# led-segment-display.net
KiCad netlist of a schematic drawn in EAGLE
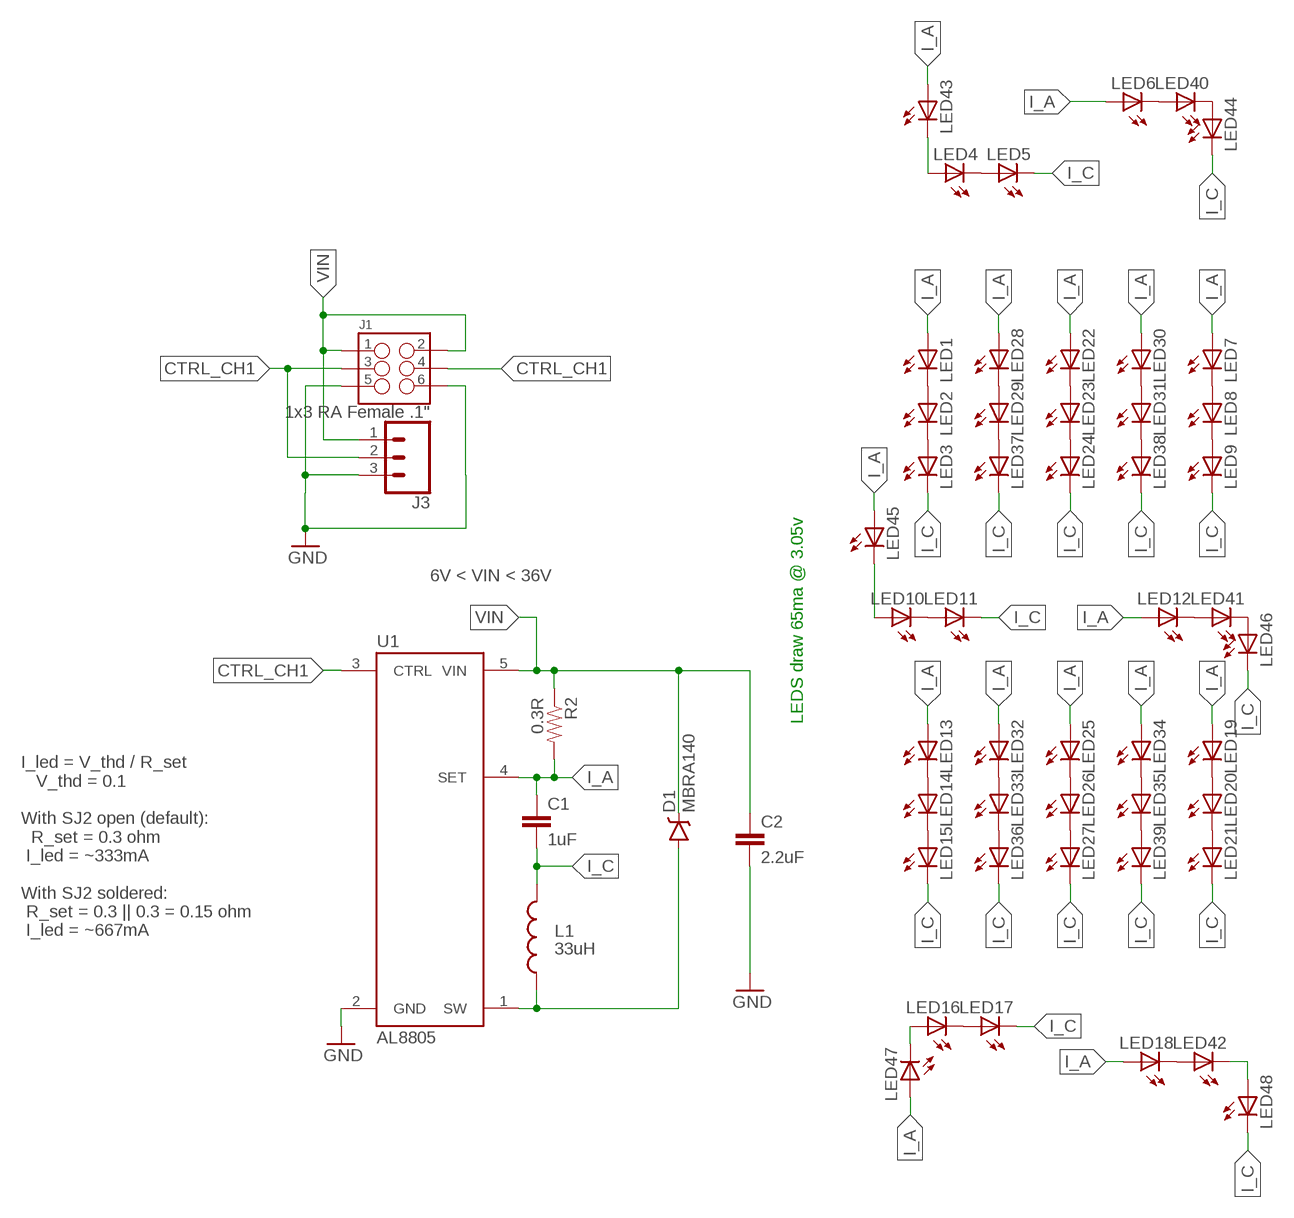
[diagram p0: schematic, sheet 1]

(export (version "E")
  (design (tool "Eeschema 10.0.6"))
  (components
    (comp (ref "C1")
      (value "1uF")
      (footprint "eagle-import:1206-CAP")
      (libsource (lib "eagle-import") (part "1.0UF50V10%(1206)"))
    )
    (comp (ref "C2")
      (value "2.2uF")
      (footprint "eagle-import:1206-CAP")
      (libsource (lib "eagle-import") (part "2.2UF50V10%(1206)"))
    )
    (comp (ref "D1")
      (value "MBRA140")
      (footprint "eagle-import:SMA-DIODE")
      (libsource (lib "eagle-import") (part "DIODE-SCHOTTKY-MBRA140"))
    )
    (comp (ref "J1")
      (value "M03X2SMD")
      (footprint "eagle-import:2X3_SMD_2.54MM")
      (libsource (lib "eagle-import") (part "M03X2SMD"))
    )
    (comp (ref "J3")
      (value "1x3 RA Female .1\"")
      (footprint "eagle-import:1X3_SMD_2.54MM")
      (libsource (lib "eagle-import") (part "CONN_03SMD_RA_2.54MM"))
    )
    (comp (ref "L1")
      (value "33uH")
      (footprint "eagle-import:SRN6045")
      (libsource (lib "eagle-import") (part "INDUCTORBOURNS_SRN6045"))
    )
    (comp (ref "LED1")
      (value "LED3014")
      (footprint "eagle-import:LED-3014")
      (libsource (lib "eagle-import") (part "LED3014"))
    )
    (comp (ref "LED2")
      (value "LED3014")
      (footprint "eagle-import:LED-3014")
      (libsource (lib "eagle-import") (part "LED3014"))
    )
    (comp (ref "LED3")
      (value "LED3014")
      (footprint "eagle-import:LED-3014")
      (libsource (lib "eagle-import") (part "LED3014"))
    )
    (comp (ref "LED4")
      (value "LED3014")
      (footprint "eagle-import:LED-3014")
      (libsource (lib "eagle-import") (part "LED3014"))
    )
    (comp (ref "LED5")
      (value "LED3014")
      (footprint "eagle-import:LED-3014")
      (libsource (lib "eagle-import") (part "LED3014"))
    )
    (comp (ref "LED6")
      (value "LED3014")
      (footprint "eagle-import:LED-3014")
      (libsource (lib "eagle-import") (part "LED3014"))
    )
    (comp (ref "LED7")
      (value "LED3014")
      (footprint "eagle-import:LED-3014")
      (libsource (lib "eagle-import") (part "LED3014"))
    )
    (comp (ref "LED8")
      (value "LED3014")
      (footprint "eagle-import:LED-3014")
      (libsource (lib "eagle-import") (part "LED3014"))
    )
    (comp (ref "LED9")
      (value "LED3014")
      (footprint "eagle-import:LED-3014")
      (libsource (lib "eagle-import") (part "LED3014"))
    )
    (comp (ref "LED10")
      (value "LED3014")
      (footprint "eagle-import:LED-3014")
      (libsource (lib "eagle-import") (part "LED3014"))
    )
    (comp (ref "LED11")
      (value "LED3014")
      (footprint "eagle-import:LED-3014")
      (libsource (lib "eagle-import") (part "LED3014"))
    )
    (comp (ref "LED12")
      (value "LED3014")
      (footprint "eagle-import:LED-3014")
      (libsource (lib "eagle-import") (part "LED3014"))
    )
    (comp (ref "LED13")
      (value "LED3014")
      (footprint "eagle-import:LED-3014")
      (libsource (lib "eagle-import") (part "LED3014"))
    )
    (comp (ref "LED14")
      (value "LED3014")
      (footprint "eagle-import:LED-3014")
      (libsource (lib "eagle-import") (part "LED3014"))
    )
    (comp (ref "LED15")
      (value "LED3014")
      (footprint "eagle-import:LED-3014")
      (libsource (lib "eagle-import") (part "LED3014"))
    )
    (comp (ref "LED16")
      (value "LED3014")
      (footprint "eagle-import:LED-3014")
      (libsource (lib "eagle-import") (part "LED3014"))
    )
    (comp (ref "LED17")
      (value "LED3014")
      (footprint "eagle-import:LED-3014")
      (libsource (lib "eagle-import") (part "LED3014"))
    )
    (comp (ref "LED18")
      (value "LED3014")
      (footprint "eagle-import:LED-3014")
      (libsource (lib "eagle-import") (part "LED3014"))
    )
    (comp (ref "LED19")
      (value "LED3014")
      (footprint "eagle-import:LED-3014")
      (libsource (lib "eagle-import") (part "LED3014"))
    )
    (comp (ref "LED20")
      (value "LED3014")
      (footprint "eagle-import:LED-3014")
      (libsource (lib "eagle-import") (part "LED3014"))
    )
    (comp (ref "LED21")
      (value "LED3014")
      (footprint "eagle-import:LED-3014")
      (libsource (lib "eagle-import") (part "LED3014"))
    )
    (comp (ref "LED22")
      (value "LED3014")
      (footprint "eagle-import:LED-3014")
      (libsource (lib "eagle-import") (part "LED3014"))
    )
    (comp (ref "LED23")
      (value "LED3014")
      (footprint "eagle-import:LED-3014")
      (libsource (lib "eagle-import") (part "LED3014"))
    )
    (comp (ref "LED24")
      (value "LED3014")
      (footprint "eagle-import:LED-3014")
      (libsource (lib "eagle-import") (part "LED3014"))
    )
    (comp (ref "LED25")
      (value "LED3014")
      (footprint "eagle-import:LED-3014")
      (libsource (lib "eagle-import") (part "LED3014"))
    )
    (comp (ref "LED26")
      (value "LED3014")
      (footprint "eagle-import:LED-3014")
      (libsource (lib "eagle-import") (part "LED3014"))
    )
    (comp (ref "LED27")
      (value "LED3014")
      (footprint "eagle-import:LED-3014")
      (libsource (lib "eagle-import") (part "LED3014"))
    )
    (comp (ref "LED28")
      (value "LED3014")
      (footprint "eagle-import:LED-3014")
      (libsource (lib "eagle-import") (part "LED3014"))
    )
    (comp (ref "LED29")
      (value "LED3014")
      (footprint "eagle-import:LED-3014")
      (libsource (lib "eagle-import") (part "LED3014"))
    )
    (comp (ref "LED30")
      (value "LED3014")
      (footprint "eagle-import:LED-3014")
      (libsource (lib "eagle-import") (part "LED3014"))
    )
    (comp (ref "LED31")
      (value "LED3014")
      (footprint "eagle-import:LED-3014")
      (libsource (lib "eagle-import") (part "LED3014"))
    )
    (comp (ref "LED32")
      (value "LED3014")
      (footprint "eagle-import:LED-3014")
      (libsource (lib "eagle-import") (part "LED3014"))
    )
    (comp (ref "LED33")
      (value "LED3014")
      (footprint "eagle-import:LED-3014")
      (libsource (lib "eagle-import") (part "LED3014"))
    )
    (comp (ref "LED34")
      (value "LED3014")
      (footprint "eagle-import:LED-3014")
      (libsource (lib "eagle-import") (part "LED3014"))
    )
    (comp (ref "LED35")
      (value "LED3014")
      (footprint "eagle-import:LED-3014")
      (libsource (lib "eagle-import") (part "LED3014"))
    )
    (comp (ref "LED36")
      (value "LED3014")
      (footprint "eagle-import:LED-3014")
      (libsource (lib "eagle-import") (part "LED3014"))
    )
    (comp (ref "LED37")
      (value "LED3014")
      (footprint "eagle-import:LED-3014")
      (libsource (lib "eagle-import") (part "LED3014"))
    )
    (comp (ref "LED38")
      (value "LED3014")
      (footprint "eagle-import:LED-3014")
      (libsource (lib "eagle-import") (part "LED3014"))
    )
    (comp (ref "LED39")
      (value "LED3014")
      (footprint "eagle-import:LED-3014")
      (libsource (lib "eagle-import") (part "LED3014"))
    )
    (comp (ref "LED40")
      (value "LED3014")
      (footprint "eagle-import:LED-3014")
      (libsource (lib "eagle-import") (part "LED3014"))
    )
    (comp (ref "LED41")
      (value "LED3014")
      (footprint "eagle-import:LED-3014")
      (libsource (lib "eagle-import") (part "LED3014"))
    )
    (comp (ref "LED42")
      (value "LED3014")
      (footprint "eagle-import:LED-3014")
      (libsource (lib "eagle-import") (part "LED3014"))
    )
    (comp (ref "LED43")
      (value "LED3014")
      (footprint "eagle-import:LED-3014")
      (libsource (lib "eagle-import") (part "LED3014"))
    )
    (comp (ref "LED44")
      (value "LED3014")
      (footprint "eagle-import:LED-3014")
      (libsource (lib "eagle-import") (part "LED3014"))
    )
    (comp (ref "LED45")
      (value "LED3014")
      (footprint "eagle-import:LED-3014")
      (libsource (lib "eagle-import") (part "LED3014"))
    )
    (comp (ref "LED46")
      (value "LED3014")
      (footprint "eagle-import:LED-3014")
      (libsource (lib "eagle-import") (part "LED3014"))
    )
    (comp (ref "LED47")
      (value "LED3014")
      (footprint "eagle-import:LED-3014")
      (libsource (lib "eagle-import") (part "LED3014"))
    )
    (comp (ref "LED48")
      (value "LED3014")
      (footprint "eagle-import:LED-3014")
      (libsource (lib "eagle-import") (part "LED3014"))
    )
    (comp (ref "R2")
      (value "0.3R")
      (footprint "eagle-import:0805")
      (libsource (lib "eagle-import") (part "0.3OHM-1/8W-1%(0805)"))
    )
    (comp (ref "U1")
      (value "AL8805")
      (footprint "eagle-import:SOT23-5")
      (libsource (lib "eagle-import") (part "AL8805"))
    )
  )
  (nets
    (net (code "1") (name "CTRL_CH1") (class "Default")
      (node (ref "J1") (pin "3") (pinfunction "3_3") (pintype "bidirectional"))
      (node (ref "J1") (pin "4") (pinfunction "4_4") (pintype "bidirectional"))
      (node (ref "J3") (pin "2") (pinfunction "2_2") (pintype "passive"))
      (node (ref "U1") (pin "3") (pinfunction "CTRL_3") (pintype "bidirectional"))
    )
    (net (code "2") (name "GND") (class "Default")
      (node (ref "C2") (pin "2") (pinfunction "2_2") (pintype "passive"))
      (node (ref "J1") (pin "5") (pinfunction "5_5") (pintype "bidirectional"))
      (node (ref "J1") (pin "6") (pinfunction "6_6") (pintype "bidirectional"))
      (node (ref "J3") (pin "3") (pinfunction "3_3") (pintype "passive"))
      (node (ref "U1") (pin "2") (pinfunction "GND_2") (pintype "bidirectional"))
    )
    (net (code "3") (name "I_A") (class "Default")
      (node (ref "C1") (pin "1") (pinfunction "1_1") (pintype "passive"))
      (node (ref "LED1") (pin "A") (pinfunction "A_A") (pintype "passive"))
      (node (ref "LED12") (pin "A") (pinfunction "A_A") (pintype "passive"))
      (node (ref "LED13") (pin "A") (pinfunction "A_A") (pintype "passive"))
      (node (ref "LED18") (pin "A") (pinfunction "A_A") (pintype "passive"))
      (node (ref "LED19") (pin "A") (pinfunction "A_A") (pintype "passive"))
      (node (ref "LED22") (pin "A") (pinfunction "A_A") (pintype "passive"))
      (node (ref "LED25") (pin "A") (pinfunction "A_A") (pintype "passive"))
      (node (ref "LED28") (pin "A") (pinfunction "A_A") (pintype "passive"))
      (node (ref "LED30") (pin "A") (pinfunction "A_A") (pintype "passive"))
      (node (ref "LED32") (pin "A") (pinfunction "A_A") (pintype "passive"))
      (node (ref "LED34") (pin "A") (pinfunction "A_A") (pintype "passive"))
      (node (ref "LED43") (pin "A") (pinfunction "A_A") (pintype "passive"))
      (node (ref "LED45") (pin "A") (pinfunction "A_A") (pintype "passive"))
      (node (ref "LED47") (pin "A") (pinfunction "A_A") (pintype "passive"))
      (node (ref "LED6") (pin "A") (pinfunction "A_A") (pintype "passive"))
      (node (ref "LED7") (pin "A") (pinfunction "A_A") (pintype "passive"))
      (node (ref "R2") (pin "2") (pinfunction "2_2") (pintype "passive"))
      (node (ref "U1") (pin "4") (pinfunction "SET_4") (pintype "bidirectional"))
    )
    (net (code "4") (name "I_C") (class "Default")
      (node (ref "C1") (pin "2") (pinfunction "2_2") (pintype "passive"))
      (node (ref "L1") (pin "2") (pinfunction "2_2") (pintype "passive"))
      (node (ref "LED11") (pin "C") (pinfunction "C_C") (pintype "passive"))
      (node (ref "LED15") (pin "C") (pinfunction "C_C") (pintype "passive"))
      (node (ref "LED17") (pin "C") (pinfunction "C_C") (pintype "passive"))
      (node (ref "LED21") (pin "C") (pinfunction "C_C") (pintype "passive"))
      (node (ref "LED24") (pin "C") (pinfunction "C_C") (pintype "passive"))
      (node (ref "LED27") (pin "C") (pinfunction "C_C") (pintype "passive"))
      (node (ref "LED3") (pin "C") (pinfunction "C_C") (pintype "passive"))
      (node (ref "LED36") (pin "C") (pinfunction "C_C") (pintype "passive"))
      (node (ref "LED37") (pin "C") (pinfunction "C_C") (pintype "passive"))
      (node (ref "LED38") (pin "C") (pinfunction "C_C") (pintype "passive"))
      (node (ref "LED39") (pin "C") (pinfunction "C_C") (pintype "passive"))
      (node (ref "LED44") (pin "C") (pinfunction "C_C") (pintype "passive"))
      (node (ref "LED46") (pin "C") (pinfunction "C_C") (pintype "passive"))
      (node (ref "LED48") (pin "C") (pinfunction "C_C") (pintype "passive"))
      (node (ref "LED5") (pin "C") (pinfunction "C_C") (pintype "passive"))
      (node (ref "LED9") (pin "C") (pinfunction "C_C") (pintype "passive"))
    )
    (net (code "5") (name "Net-(LED1-PadC)") (class "Default")
      (node (ref "LED1") (pin "C") (pinfunction "C_C") (pintype "passive"))
      (node (ref "LED2") (pin "A") (pinfunction "A_A") (pintype "passive"))
    )
    (net (code "6") (name "Net-(LED2-PadC)") (class "Default")
      (node (ref "LED2") (pin "C") (pinfunction "C_C") (pintype "passive"))
      (node (ref "LED3") (pin "A") (pinfunction "A_A") (pintype "passive"))
    )
    (net (code "7") (name "Net-(LED4-PadA)") (class "Default")
      (node (ref "LED4") (pin "A") (pinfunction "A_A") (pintype "passive"))
      (node (ref "LED43") (pin "C") (pinfunction "C_C") (pintype "passive"))
    )
    (net (code "8") (name "Net-(LED4-PadC)") (class "Default")
      (node (ref "LED4") (pin "C") (pinfunction "C_C") (pintype "passive"))
      (node (ref "LED5") (pin "A") (pinfunction "A_A") (pintype "passive"))
    )
    (net (code "9") (name "Net-(LED7-PadC)") (class "Default")
      (node (ref "LED7") (pin "C") (pinfunction "C_C") (pintype "passive"))
      (node (ref "LED8") (pin "A") (pinfunction "A_A") (pintype "passive"))
    )
    (net (code "10") (name "Net-(LED8-PadC)") (class "Default")
      (node (ref "LED8") (pin "C") (pinfunction "C_C") (pintype "passive"))
      (node (ref "LED9") (pin "A") (pinfunction "A_A") (pintype "passive"))
    )
    (net (code "11") (name "Net-(LED10-PadA)") (class "Default")
      (node (ref "LED10") (pin "A") (pinfunction "A_A") (pintype "passive"))
      (node (ref "LED45") (pin "C") (pinfunction "C_C") (pintype "passive"))
    )
    (net (code "12") (name "Net-(LED10-PadC)") (class "Default")
      (node (ref "LED10") (pin "C") (pinfunction "C_C") (pintype "passive"))
      (node (ref "LED11") (pin "A") (pinfunction "A_A") (pintype "passive"))
    )
    (net (code "13") (name "Net-(LED12-PadC)") (class "Default")
      (node (ref "LED12") (pin "C") (pinfunction "C_C") (pintype "passive"))
      (node (ref "LED41") (pin "A") (pinfunction "A_A") (pintype "passive"))
    )
    (net (code "14") (name "Net-(LED13-PadC)") (class "Default")
      (node (ref "LED13") (pin "C") (pinfunction "C_C") (pintype "passive"))
      (node (ref "LED14") (pin "A") (pinfunction "A_A") (pintype "passive"))
    )
    (net (code "15") (name "Net-(LED14-PadC)") (class "Default")
      (node (ref "LED14") (pin "C") (pinfunction "C_C") (pintype "passive"))
      (node (ref "LED15") (pin "A") (pinfunction "A_A") (pintype "passive"))
    )
    (net (code "16") (name "Net-(LED16-PadA)") (class "Default")
      (node (ref "LED16") (pin "A") (pinfunction "A_A") (pintype "passive"))
      (node (ref "LED47") (pin "C") (pinfunction "C_C") (pintype "passive"))
    )
    (net (code "17") (name "Net-(LED16-PadC)") (class "Default")
      (node (ref "LED16") (pin "C") (pinfunction "C_C") (pintype "passive"))
      (node (ref "LED17") (pin "A") (pinfunction "A_A") (pintype "passive"))
    )
    (net (code "18") (name "Net-(LED18-PadC)") (class "Default")
      (node (ref "LED18") (pin "C") (pinfunction "C_C") (pintype "passive"))
      (node (ref "LED42") (pin "A") (pinfunction "A_A") (pintype "passive"))
    )
    (net (code "19") (name "Net-(LED19-PadC)") (class "Default")
      (node (ref "LED19") (pin "C") (pinfunction "C_C") (pintype "passive"))
      (node (ref "LED20") (pin "A") (pinfunction "A_A") (pintype "passive"))
    )
    (net (code "20") (name "Net-(LED20-PadC)") (class "Default")
      (node (ref "LED20") (pin "C") (pinfunction "C_C") (pintype "passive"))
      (node (ref "LED21") (pin "A") (pinfunction "A_A") (pintype "passive"))
    )
    (net (code "21") (name "Net-(LED22-PadC)") (class "Default")
      (node (ref "LED22") (pin "C") (pinfunction "C_C") (pintype "passive"))
      (node (ref "LED23") (pin "A") (pinfunction "A_A") (pintype "passive"))
    )
    (net (code "22") (name "Net-(LED23-PadC)") (class "Default")
      (node (ref "LED23") (pin "C") (pinfunction "C_C") (pintype "passive"))
      (node (ref "LED24") (pin "A") (pinfunction "A_A") (pintype "passive"))
    )
    (net (code "23") (name "Net-(LED25-PadC)") (class "Default")
      (node (ref "LED25") (pin "C") (pinfunction "C_C") (pintype "passive"))
      (node (ref "LED26") (pin "A") (pinfunction "A_A") (pintype "passive"))
    )
    (net (code "24") (name "Net-(LED26-PadC)") (class "Default")
      (node (ref "LED26") (pin "C") (pinfunction "C_C") (pintype "passive"))
      (node (ref "LED27") (pin "A") (pinfunction "A_A") (pintype "passive"))
    )
    (net (code "25") (name "Net-(LED28-PadC)") (class "Default")
      (node (ref "LED28") (pin "C") (pinfunction "C_C") (pintype "passive"))
      (node (ref "LED29") (pin "A") (pinfunction "A_A") (pintype "passive"))
    )
    (net (code "26") (name "Net-(LED29-PadC)") (class "Default")
      (node (ref "LED29") (pin "C") (pinfunction "C_C") (pintype "passive"))
      (node (ref "LED37") (pin "A") (pinfunction "A_A") (pintype "passive"))
    )
    (net (code "27") (name "Net-(LED30-PadC)") (class "Default")
      (node (ref "LED30") (pin "C") (pinfunction "C_C") (pintype "passive"))
      (node (ref "LED31") (pin "A") (pinfunction "A_A") (pintype "passive"))
    )
    (net (code "28") (name "Net-(LED31-PadC)") (class "Default")
      (node (ref "LED31") (pin "C") (pinfunction "C_C") (pintype "passive"))
      (node (ref "LED38") (pin "A") (pinfunction "A_A") (pintype "passive"))
    )
    (net (code "29") (name "Net-(LED32-PadC)") (class "Default")
      (node (ref "LED32") (pin "C") (pinfunction "C_C") (pintype "passive"))
      (node (ref "LED33") (pin "A") (pinfunction "A_A") (pintype "passive"))
    )
    (net (code "30") (name "Net-(LED33-PadC)") (class "Default")
      (node (ref "LED33") (pin "C") (pinfunction "C_C") (pintype "passive"))
      (node (ref "LED36") (pin "A") (pinfunction "A_A") (pintype "passive"))
    )
    (net (code "31") (name "Net-(LED34-PadC)") (class "Default")
      (node (ref "LED34") (pin "C") (pinfunction "C_C") (pintype "passive"))
      (node (ref "LED35") (pin "A") (pinfunction "A_A") (pintype "passive"))
    )
    (net (code "32") (name "Net-(LED35-PadC)") (class "Default")
      (node (ref "LED35") (pin "C") (pinfunction "C_C") (pintype "passive"))
      (node (ref "LED39") (pin "A") (pinfunction "A_A") (pintype "passive"))
    )
    (net (code "33") (name "Net-(LED40-PadA)") (class "Default")
      (node (ref "LED40") (pin "A") (pinfunction "A_A") (pintype "passive"))
      (node (ref "LED6") (pin "C") (pinfunction "C_C") (pintype "passive"))
    )
    (net (code "34") (name "Net-(LED40-PadC)") (class "Default")
      (node (ref "LED40") (pin "C") (pinfunction "C_C") (pintype "passive"))
      (node (ref "LED44") (pin "A") (pinfunction "A_A") (pintype "passive"))
    )
    (net (code "35") (name "Net-(LED41-PadC)") (class "Default")
      (node (ref "LED41") (pin "C") (pinfunction "C_C") (pintype "passive"))
      (node (ref "LED46") (pin "A") (pinfunction "A_A") (pintype "passive"))
    )
    (net (code "36") (name "Net-(LED42-PadC)") (class "Default")
      (node (ref "LED42") (pin "C") (pinfunction "C_C") (pintype "passive"))
      (node (ref "LED48") (pin "A") (pinfunction "A_A") (pintype "passive"))
    )
    (net (code "37") (name "Net-(U1-SW)") (class "Default")
      (node (ref "D1") (pin "A") (pinfunction "A_A") (pintype "passive"))
      (node (ref "L1") (pin "1") (pinfunction "1_1") (pintype "passive"))
      (node (ref "U1") (pin "1") (pinfunction "SW_1") (pintype "bidirectional"))
    )
    (net (code "38") (name "VIN") (class "Default")
      (node (ref "C2") (pin "1") (pinfunction "1_1") (pintype "passive"))
      (node (ref "D1") (pin "C") (pinfunction "C_C") (pintype "passive"))
      (node (ref "J1") (pin "1") (pinfunction "1_1") (pintype "bidirectional"))
      (node (ref "J1") (pin "2") (pinfunction "2_2") (pintype "bidirectional"))
      (node (ref "J3") (pin "1") (pinfunction "1_1") (pintype "passive"))
      (node (ref "R2") (pin "1") (pinfunction "1_1") (pintype "passive"))
      (node (ref "U1") (pin "5") (pinfunction "VIN_5") (pintype "bidirectional"))
    )
  )
)
